# design.net
KiCad netlist of a schematic drawn in Altium Designer
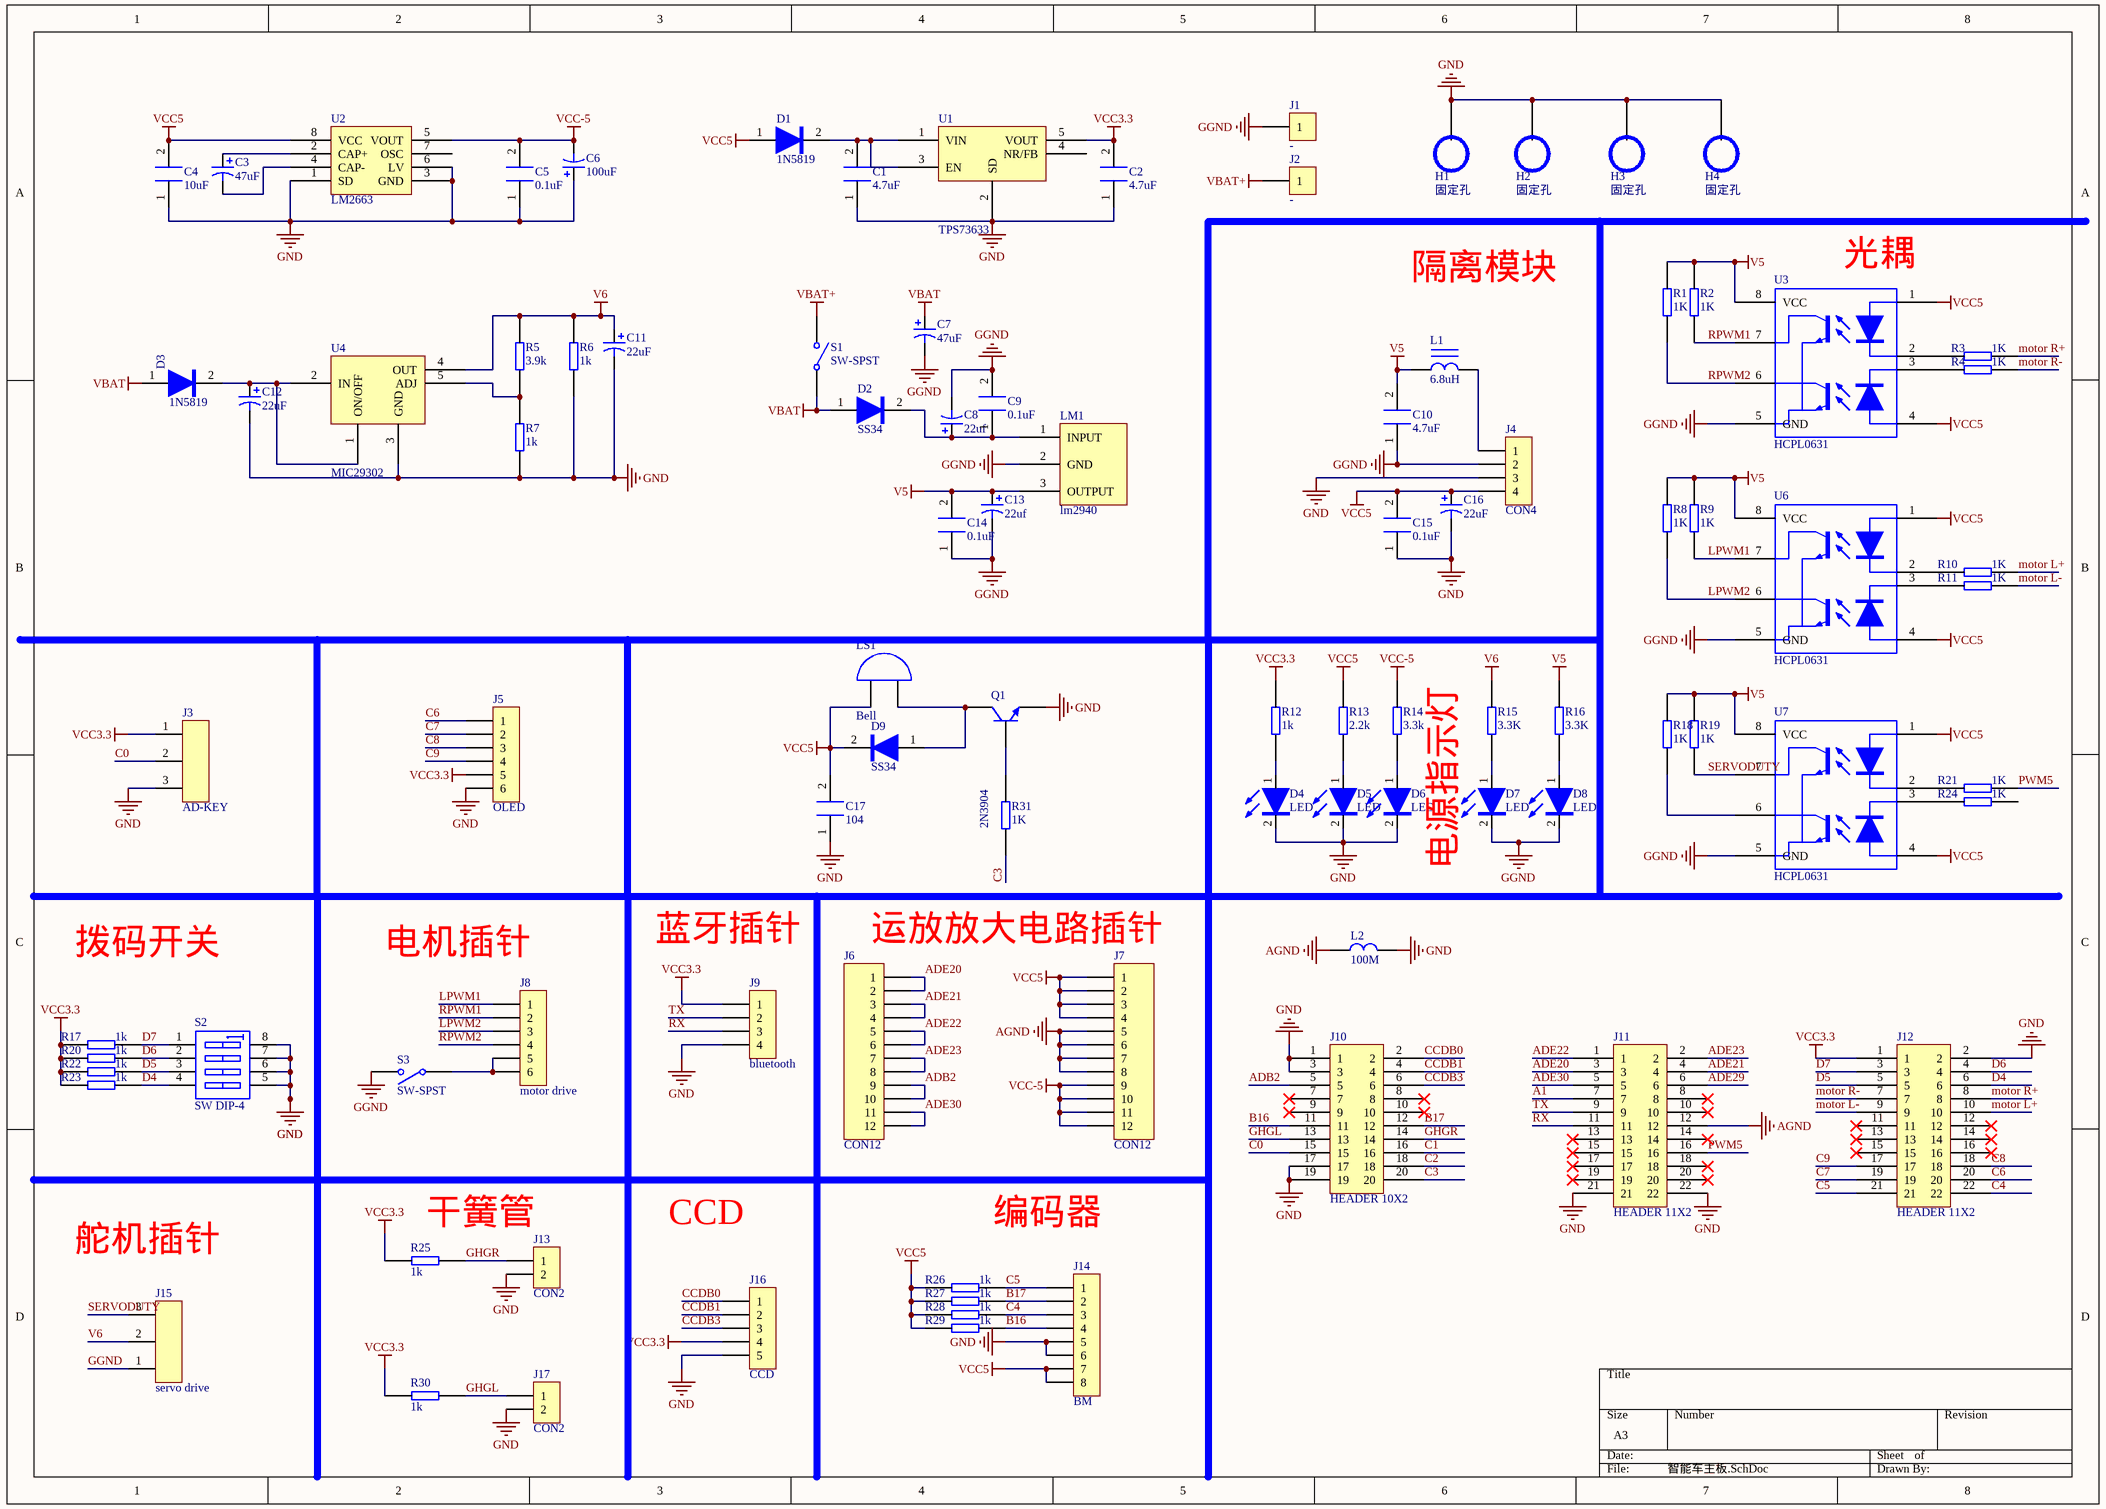
[diagram p0: 智能车主板.SchDoc]

(export (version "E")
  (design (tool "Eeschema 10.0.6"))
  (components
    (comp (ref "C1")
      (value "4.7uF")
      (footprint "0805C")
      (description "电容")
      (libsource (lib "智能车主板") (part "CAP"))
    )
    (comp (ref "C2")
      (value "4.7uF")
      (footprint "0805C")
      (description "电容")
      (libsource (lib "智能车主板") (part "CAP"))
    )
    (comp (ref "C3")
      (value "47uF")
      (footprint "C型钽电容_6032_28")
      (description "极性电容")
      (libsource (lib "智能车主板") (part "极性电容"))
    )
    (comp (ref "C4")
      (value "10uF")
      (footprint "0805C")
      (description "电容")
      (libsource (lib "智能车主板") (part "CAP"))
    )
    (comp (ref "C5")
      (value "0.1uF")
      (footprint "0805C")
      (description "电容")
      (libsource (lib "智能车主板") (part "CAP"))
    )
    (comp (ref "C6")
      (value "100uF")
      (footprint "D型钽电容_7343_31")
      (description "极性电容")
      (libsource (lib "智能车主板") (part "极性电容"))
    )
    (comp (ref "C7")
      (value "47uF")
      (footprint "D型钽电容_7343_31")
      (description "极性电容")
      (libsource (lib "") (part "极性电容_1"))
    )
    (comp (ref "C8")
      (value "22uf")
      (footprint "C型钽电容_6032_28")
      (description "极性电容")
      (libsource (lib "智能车主板") (part "极性电容"))
    )
    (comp (ref "C9")
      (value "0.1uF")
      (footprint "0805C")
      (description "电容")
      (libsource (lib "智能车主板") (part "CAP"))
    )
    (comp (ref "C10")
      (value "4.7uF")
      (footprint "0805C")
      (description "电容")
      (libsource (lib "智能车主板") (part "CAP"))
    )
    (comp (ref "C11")
      (value "22uF")
      (footprint "B型钽电容_3528_21")
      (description "极性电容")
      (libsource (lib "智能车主板") (part "极性电容"))
    )
    (comp (ref "C12")
      (value "22uF")
      (footprint "B型钽电容_3528_21")
      (description "极性电容")
      (libsource (lib "智能车主板") (part "极性电容"))
    )
    (comp (ref "C13")
      (value "22uf")
      (footprint "B型钽电容_3528_21")
      (description "极性电容")
      (libsource (lib "智能车主板") (part "极性电容"))
    )
    (comp (ref "C14")
      (value "0.1uF")
      (footprint "0805C")
      (description "电容")
      (libsource (lib "智能车主板") (part "CAP"))
    )
    (comp (ref "C15")
      (value "0.1uF")
      (footprint "0805C")
      (description "电容")
      (libsource (lib "智能车主板") (part "CAP"))
    )
    (comp (ref "C16")
      (value "22uF")
      (footprint "B型钽电容_3528_21")
      (description "极性电容")
      (libsource (lib "") (part "极性电容_1"))
    )
    (comp (ref "C17")
      (value "104")
      (footprint "0805C")
      (description "电容")
      (libsource (lib "智能车主板") (part "CAP"))
    )
    (comp (ref "D1")
      (value "1N5819")
      (footprint "0805D")
      (description "二极管")
      (libsource (lib "智能车主板") (part "SS34"))
    )
    (comp (ref "D2")
      (value "SS34")
      (footprint "0805D")
      (description "二极管")
      (libsource (lib "智能车主板") (part "SS34"))
    )
    (comp (ref "D3")
      (value "1N5819")
      (footprint "0805D")
      (description "二极管")
      (libsource (lib "智能车主板") (part "SS34"))
    )
    (comp (ref "D4") (value "LED") (footprint "0805D") (libsource (lib "智能车主板") (part "LED")))
    (comp (ref "D5") (value "LED") (footprint "0805D") (libsource (lib "智能车主板") (part "LED")))
    (comp (ref "D6") (value "LED") (footprint "0805D") (libsource (lib "智能车主板") (part "LED")))
    (comp (ref "D7") (value "LED") (footprint "0805D") (libsource (lib "智能车主板") (part "LED")))
    (comp (ref "D8") (value "LED") (footprint "0805D") (libsource (lib "智能车主板") (part "LED")))
    (comp (ref "D9")
      (value "SS34")
      (footprint "SS34_3D")
      (description "二极管")
      (libsource (lib "智能车主板") (part "SS34"))
    )
    (comp (ref "H1") (value "固定孔") (footprint "铜柱孔3") (libsource (lib "智能车主板") (part "固定孔")))
    (comp (ref "H2") (value "固定孔") (footprint "铜柱孔3") (libsource (lib "智能车主板") (part "固定孔")))
    (comp (ref "H3") (value "固定孔") (footprint "铜柱孔3") (libsource (lib "智能车主板") (part "固定孔")))
    (comp (ref "H4") (value "固定孔") (footprint "铜柱孔3") (libsource (lib "智能车主板") (part "固定孔")))
    (comp (ref "J1")
      (value "-")
      (footprint "单面焊盘2*3MM_1PIN")
      (description "Connector")
      (libsource (lib "智能车主板") (part "CON1"))
    )
    (comp (ref "J2")
      (value "-")
      (footprint "单面焊盘2*3MM_1PIN")
      (description "Connector")
      (libsource (lib "智能车主板") (part "CON1"))
    )
    (comp (ref "J3")
      (value "AD-KEY")
      (footprint "HDR1X3")
      (description "SOCKET")
      (libsource (lib "") (part "CON3_1"))
    )
    (comp (ref "J4")
      (value "CON4")
      (footprint "B0505S-2W")
      (description "Connector")
      (libsource (lib "智能车主板") (part "CON4"))
    )
    (comp (ref "J5")
      (value "OLED")
      (footprint "HDR1X6")
      (description "Connector")
      (libsource (lib "智能车主板") (part "CON6"))
    )
    (comp (ref "J6")
      (value "CON12")
      (footprint "HDR2X6")
      (description "Connector")
      (libsource (lib "智能车主板") (part "CON12"))
    )
    (comp (ref "J7")
      (value "CON12")
      (footprint "HDR2X6")
      (description "Connector")
      (libsource (lib "") (part "CON12_1"))
    )
    (comp (ref "J8")
      (value "motor drive")
      (footprint "HDR2X3")
      (description "Connector")
      (libsource (lib "智能车主板") (part "CON6"))
    )
    (comp (ref "J9")
      (value "bluetooth")
      (footprint "HDR1X4")
      (description "Connector")
      (libsource (lib "智能车主板") (part "CON4"))
    )
    (comp (ref "J10")
      (value "HEADER 10X2")
      (footprint "HDR2X10")
      (description "排针")
      (libsource (lib "智能车主板") (part "HEADER 10X2"))
    )
    (comp (ref "J11")
      (value "HEADER 11X2")
      (footprint "HDR2X11")
      (description "排针")
      (libsource (lib "智能车主板") (part "HEADER 11X2"))
    )
    (comp (ref "J12")
      (value "HEADER 11X2")
      (footprint "HDR2X11")
      (description "排针")
      (libsource (lib "智能车主板") (part "HEADER 11X2"))
    )
    (comp (ref "J13")
      (value "CON2")
      (footprint "2PIN杜邦插座_1.27mm")
      (description "Connector")
      (libsource (lib "智能车主板") (part "CON2"))
    )
    (comp (ref "J14")
      (value "BM")
      (footprint "HDR2X4")
      (description "Connector")
      (libsource (lib "智能车主板") (part "CON8"))
    )
    (comp (ref "J15")
      (value "servo drive")
      (footprint "HDR1X3")
      (description "SOCKET")
      (libsource (lib "智能车主板") (part "CON3"))
    )
    (comp (ref "J16")
      (value "CCD")
      (footprint "HDR1X5")
      (description "Connector")
      (libsource (lib "智能车主板") (part "CON5"))
    )
    (comp (ref "J17")
      (value "CON2")
      (footprint "2PIN杜邦插座_1.27mm")
      (description "Connector")
      (libsource (lib "智能车主板") (part "CON2"))
    )
    (comp (ref "L1")
      (value "6.8uH")
      (footprint "CDRH3D16_4.2*1.8")
      (description "电感")
      (libsource (lib "智能车主板") (part "INDUCTOR"))
    )
    (comp (ref "L2") (value "100M") (footprint "0603L") (libsource (lib "智能车主板") (part "INDUCTOR_2")))
    (comp (ref "LM1")
      (value "lm2940")
      (footprint "SOT-223")
      (description "IC")
      (libsource (lib "智能车主板") (part "lm2940"))
    )
    (comp (ref "LS1")
      (value "Bell")
      (footprint "蜂鸣器侧装")
      (description "Electrical Bell")
      (fields (field (name "PUBLISHER") "Altium Limited"))
      (libsource (lib "智能车主板") (part "Bell"))
    )
    (comp (ref "Q1")
      (value "2N3904")
      (footprint "TO-92A")
      (description "NPN General Purpose Amplifier")
      (fields (field (name "PUBLISHER") "Altium Limited"))
      (libsource (lib "智能车主板") (part "2N3904"))
    )
    (comp (ref "R1")
      (value "1K")
      (footprint "0805R")
      (description "电阻")
      (libsource (lib "智能车主板") (part "RES"))
    )
    (comp (ref "R2")
      (value "1K")
      (footprint "0805R")
      (description "电阻")
      (libsource (lib "智能车主板") (part "RES"))
    )
    (comp (ref "R3")
      (value "1K")
      (footprint "0805R")
      (description "电阻")
      (libsource (lib "智能车主板") (part "RES"))
    )
    (comp (ref "R4")
      (value "1K")
      (footprint "0805R")
      (description "电阻")
      (libsource (lib "智能车主板") (part "RES"))
    )
    (comp (ref "R5")
      (value "3.9k")
      (footprint "0805R")
      (description "电阻")
      (libsource (lib "智能车主板") (part "RES"))
    )
    (comp (ref "R6")
      (value "1k")
      (footprint "0805R")
      (description "电阻")
      (libsource (lib "智能车主板") (part "RES"))
    )
    (comp (ref "R7")
      (value "1k")
      (footprint "0805R")
      (description "电阻")
      (libsource (lib "智能车主板") (part "RES"))
    )
    (comp (ref "R8")
      (value "1K")
      (footprint "0805R")
      (description "电阻")
      (libsource (lib "智能车主板") (part "RES"))
    )
    (comp (ref "R9")
      (value "1K")
      (footprint "0805R")
      (description "电阻")
      (libsource (lib "智能车主板") (part "RES"))
    )
    (comp (ref "R10")
      (value "1K")
      (footprint "0805R")
      (description "电阻")
      (libsource (lib "智能车主板") (part "RES"))
    )
    (comp (ref "R11")
      (value "1K")
      (footprint "0805R")
      (description "电阻")
      (libsource (lib "智能车主板") (part "RES"))
    )
    (comp (ref "R12")
      (value "1k")
      (footprint "0603R")
      (description "电阻")
      (libsource (lib "智能车主板") (part "RES"))
    )
    (comp (ref "R13")
      (value "2.2k")
      (footprint "0603R")
      (description "电阻")
      (libsource (lib "智能车主板") (part "RES"))
    )
    (comp (ref "R14")
      (value "3.3k")
      (footprint "0603R")
      (description "电阻")
      (libsource (lib "智能车主板") (part "RES"))
    )
    (comp (ref "R15")
      (value "3.3K")
      (footprint "0603R")
      (description "电阻")
      (libsource (lib "智能车主板") (part "RES"))
    )
    (comp (ref "R16")
      (value "3.3K")
      (footprint "0603R")
      (description "电阻")
      (libsource (lib "智能车主板") (part "RES"))
    )
    (comp (ref "R17")
      (value "1k")
      (footprint "0603R")
      (description "电阻")
      (libsource (lib "智能车主板") (part "RES"))
    )
    (comp (ref "R18")
      (value "1K")
      (footprint "0805R")
      (description "电阻")
      (libsource (lib "智能车主板") (part "RES"))
    )
    (comp (ref "R19")
      (value "1K")
      (footprint "0805R")
      (description "电阻")
      (libsource (lib "智能车主板") (part "RES"))
    )
    (comp (ref "R20")
      (value "1k")
      (footprint "0603R")
      (description "电阻")
      (libsource (lib "智能车主板") (part "RES"))
    )
    (comp (ref "R21")
      (value "1K")
      (footprint "0805R")
      (description "电阻")
      (libsource (lib "智能车主板") (part "RES"))
    )
    (comp (ref "R22")
      (value "1k")
      (footprint "0603R")
      (description "电阻")
      (libsource (lib "智能车主板") (part "RES"))
    )
    (comp (ref "R23")
      (value "1k")
      (footprint "0603R")
      (description "电阻")
      (libsource (lib "智能车主板") (part "RES"))
    )
    (comp (ref "R24")
      (value "1K")
      (footprint "0805R")
      (description "电阻")
      (libsource (lib "智能车主板") (part "RES"))
    )
    (comp (ref "R25")
      (value "1k")
      (footprint "0603R")
      (description "电阻")
      (libsource (lib "智能车主板") (part "RES"))
    )
    (comp (ref "R26")
      (value "1k")
      (footprint "0805R")
      (description "电阻")
      (libsource (lib "智能车主板") (part "RES"))
    )
    (comp (ref "R27")
      (value "1k")
      (footprint "0805R")
      (description "电阻")
      (libsource (lib "智能车主板") (part "RES"))
    )
    (comp (ref "R28")
      (value "1k")
      (footprint "0805R")
      (description "电阻")
      (libsource (lib "智能车主板") (part "RES"))
    )
    (comp (ref "R29")
      (value "1k")
      (footprint "0805R")
      (description "电阻")
      (libsource (lib "智能车主板") (part "RES"))
    )
    (comp (ref "R30")
      (value "1k")
      (footprint "0603R")
      (description "电阻")
      (libsource (lib "智能车主板") (part "RES"))
    )
    (comp (ref "R31")
      (value "1K")
      (footprint "0805R")
      (description "电阻")
      (libsource (lib "智能车主板") (part "RES"))
    )
    (comp (ref "S1")
      (value "SW-SPST")
      (footprint "开关")
      (description "Single-Pole, Single-Throw Switch")
      (fields (field (name "PUBLISHER") "Altium Limited"))
      (libsource (lib "智能车主板") (part "SW-SPST"))
    )
    (comp (ref "S2")
      (value "SW DIP-4")
      (footprint "4路拨码开关")
      (description "DIP Switch")
      (libsource (lib "智能车主板") (part "SW DIP-4"))
    )
    (comp (ref "S3")
      (value "SW-SPST")
      (footprint "开关")
      (description "Single-Pole, Single-Throw Switch")
      (fields (field (name "PUBLISHER") "Altium Limited"))
      (libsource (lib "智能车主板") (part "SW-SPST"))
    )
    (comp (ref "U1")
      (value "TPS73633")
      (footprint "SOT23_5-LEADS")
      (description "IC")
      (libsource (lib "智能车主板") (part "TPS73633"))
    )
    (comp (ref "U2")
      (value "LM2663")
      (footprint "SOP_8(OPA)")
      (description "IC")
      (libsource (lib "智能车主板") (part "LM2663"))
    )
    (comp (ref "U3")
      (value "HCPL0631")
      (footprint "SOP_8(OPA)")
      (description "光耦")
      (libsource (lib "智能车主板") (part "HCPL0631"))
    )
    (comp (ref "U4")
      (value "MIC29302")
      (footprint "TO_263_5(10.5*8.4mm)")
      (description "IC")
      (libsource (lib "智能车主板") (part "MIC29302"))
    )
    (comp (ref "U6")
      (value "HCPL0631")
      (footprint "SOP_8(OPA)")
      (description "光耦")
      (libsource (lib "智能车主板") (part "HCPL0631"))
    )
    (comp (ref "U7")
      (value "HCPL0631")
      (footprint "SOP_8(OPA)")
      (description "光耦")
      (libsource (lib "智能车主板") (part "HCPL0631"))
    )
  )
  (nets
    (net (code "1") (name "/A1") (class "Default")
      (node (ref "J11") (pin "7") (pinfunction "7_7") (pintype "passive"))
    )
    (net (code "2") (name "/ADB2") (class "Default")
      (node (ref "J10") (pin "5") (pinfunction "5_5") (pintype "passive"))
      (node (ref "J6") (pin "10") (pinfunction "10_10") (pintype "passive"))
      (node (ref "J6") (pin "9") (pinfunction "9_9") (pintype "passive"))
    )
    (net (code "3") (name "/ADE20") (class "Default")
      (node (ref "J11") (pin "3") (pinfunction "3_3") (pintype "passive"))
      (node (ref "J6") (pin "1") (pinfunction "1_1") (pintype "passive"))
      (node (ref "J6") (pin "2") (pinfunction "2_2") (pintype "passive"))
    )
    (net (code "4") (name "/ADE21") (class "Default")
      (node (ref "J11") (pin "4") (pinfunction "4_4") (pintype "passive"))
      (node (ref "J6") (pin "3") (pinfunction "3_3") (pintype "passive"))
      (node (ref "J6") (pin "4") (pinfunction "4_4") (pintype "passive"))
    )
    (net (code "5") (name "/ADE22") (class "Default")
      (node (ref "J11") (pin "1") (pinfunction "1_1") (pintype "passive"))
      (node (ref "J6") (pin "5") (pinfunction "5_5") (pintype "passive"))
      (node (ref "J6") (pin "6") (pinfunction "6_6") (pintype "passive"))
    )
    (net (code "6") (name "/ADE23") (class "Default")
      (node (ref "J11") (pin "2") (pinfunction "2_2") (pintype "passive"))
      (node (ref "J6") (pin "7") (pinfunction "7_7") (pintype "passive"))
      (node (ref "J6") (pin "8") (pinfunction "8_8") (pintype "passive"))
    )
    (net (code "7") (name "/ADE29") (class "Default")
      (node (ref "J11") (pin "6") (pinfunction "6_6") (pintype "passive"))
    )
    (net (code "8") (name "/ADE30") (class "Default")
      (node (ref "J11") (pin "5") (pinfunction "5_5") (pintype "passive"))
      (node (ref "J6") (pin "11") (pinfunction "11_11") (pintype "passive"))
      (node (ref "J6") (pin "12") (pinfunction "12_12") (pintype "passive"))
    )
    (net (code "9") (name "/B16") (class "Default")
      (node (ref "J10") (pin "11") (pinfunction "11_11") (pintype "passive"))
      (node (ref "J14") (pin "4") (pinfunction "4_4") (pintype "passive"))
      (node (ref "R29") (pin "1") (pinfunction "1_1") (pintype "passive"))
    )
    (net (code "10") (name "/B17") (class "Default")
      (node (ref "J10") (pin "12") (pinfunction "12_12") (pintype "passive"))
      (node (ref "J14") (pin "2") (pinfunction "2_2") (pintype "passive"))
      (node (ref "R27") (pin "1") (pinfunction "1_1") (pintype "passive"))
    )
    (net (code "11") (name "/C0") (class "Default")
      (node (ref "J10") (pin "15") (pinfunction "15_15") (pintype "passive"))
      (node (ref "J3") (pin "2") (pinfunction "2_2") (pintype "passive"))
    )
    (net (code "12") (name "/C1") (class "Default")
      (node (ref "J10") (pin "16") (pinfunction "16_16") (pintype "passive"))
    )
    (net (code "13") (name "/C2") (class "Default")
      (node (ref "J10") (pin "18") (pinfunction "18_18") (pintype "passive"))
    )
    (net (code "14") (name "/C3") (class "Default")
      (node (ref "J10") (pin "20") (pinfunction "20_20") (pintype "passive"))
      (node (ref "R31") (pin "1") (pinfunction "1_1") (pintype "passive"))
    )
    (net (code "15") (name "/C4") (class "Default")
      (node (ref "J12") (pin "22") (pinfunction "22_22") (pintype "passive"))
      (node (ref "J14") (pin "3") (pinfunction "3_3") (pintype "passive"))
      (node (ref "R28") (pin "1") (pinfunction "1_1") (pintype "passive"))
    )
    (net (code "16") (name "/C5") (class "Default")
      (node (ref "J12") (pin "21") (pinfunction "21_21") (pintype "passive"))
      (node (ref "J14") (pin "1") (pinfunction "1_1") (pintype "passive"))
      (node (ref "R26") (pin "1") (pinfunction "1_1") (pintype "passive"))
    )
    (net (code "17") (name "/C6") (class "Default")
      (node (ref "J12") (pin "20") (pinfunction "20_20") (pintype "passive"))
      (node (ref "J5") (pin "1") (pinfunction "1_1") (pintype "passive"))
    )
    (net (code "18") (name "/C7") (class "Default")
      (node (ref "J12") (pin "19") (pinfunction "19_19") (pintype "passive"))
      (node (ref "J5") (pin "2") (pinfunction "2_2") (pintype "passive"))
    )
    (net (code "19") (name "/C8") (class "Default")
      (node (ref "J12") (pin "18") (pinfunction "18_18") (pintype "passive"))
      (node (ref "J5") (pin "3") (pinfunction "3_3") (pintype "passive"))
    )
    (net (code "20") (name "/C9") (class "Default")
      (node (ref "J12") (pin "17") (pinfunction "17_17") (pintype "passive"))
      (node (ref "J5") (pin "4") (pinfunction "4_4") (pintype "passive"))
    )
    (net (code "21") (name "/CCDB0") (class "Default")
      (node (ref "J10") (pin "2") (pinfunction "2_2") (pintype "passive"))
      (node (ref "J16") (pin "1") (pinfunction "1_1") (pintype "passive"))
    )
    (net (code "22") (name "/CCDB1") (class "Default")
      (node (ref "J10") (pin "4") (pinfunction "4_4") (pintype "passive"))
      (node (ref "J16") (pin "2") (pinfunction "2_2") (pintype "passive"))
    )
    (net (code "23") (name "/CCDB3") (class "Default")
      (node (ref "J10") (pin "6") (pinfunction "6_6") (pintype "passive"))
      (node (ref "J16") (pin "3") (pinfunction "3_3") (pintype "passive"))
    )
    (net (code "24") (name "/D4") (class "Default")
      (node (ref "J12") (pin "6") (pinfunction "6_6") (pintype "passive"))
      (node (ref "R23") (pin "1") (pinfunction "1_1") (pintype "passive"))
      (node (ref "S2") (pin "4") (pinfunction "A4_4") (pintype "passive"))
    )
    (net (code "25") (name "/D5") (class "Default")
      (node (ref "J12") (pin "5") (pinfunction "5_5") (pintype "passive"))
      (node (ref "R22") (pin "1") (pinfunction "1_1") (pintype "passive"))
      (node (ref "S2") (pin "3") (pinfunction "A3_3") (pintype "passive"))
    )
    (net (code "26") (name "/D6") (class "Default")
      (node (ref "J12") (pin "4") (pinfunction "4_4") (pintype "passive"))
      (node (ref "R20") (pin "1") (pinfunction "1_1") (pintype "passive"))
      (node (ref "S2") (pin "2") (pinfunction "A2_2") (pintype "passive"))
    )
    (net (code "27") (name "/D7") (class "Default")
      (node (ref "J12") (pin "3") (pinfunction "3_3") (pintype "passive"))
      (node (ref "R17") (pin "1") (pinfunction "1_1") (pintype "passive"))
      (node (ref "S2") (pin "1") (pinfunction "A1_1") (pintype "passive"))
    )
    (net (code "28") (name "/GHGL") (class "Default")
      (node (ref "J10") (pin "13") (pinfunction "13_13") (pintype "passive"))
      (node (ref "J17") (pin "1") (pinfunction "1_1") (pintype "passive"))
      (node (ref "R30") (pin "1") (pinfunction "1_1") (pintype "passive"))
    )
    (net (code "29") (name "/GHGR") (class "Default")
      (node (ref "J10") (pin "14") (pinfunction "14_14") (pintype "passive"))
      (node (ref "J13") (pin "1") (pinfunction "1_1") (pintype "passive"))
      (node (ref "R25") (pin "1") (pinfunction "1_1") (pintype "passive"))
    )
    (net (code "30") (name "/LPWM1") (class "Default")
      (node (ref "J8") (pin "1") (pinfunction "1_1") (pintype "passive"))
      (node (ref "R9") (pin "1") (pinfunction "1_1") (pintype "passive"))
      (node (ref "U6") (pin "7") (pinfunction "7_7") (pintype "passive"))
    )
    (net (code "31") (name "/LPWM2") (class "Default")
      (node (ref "J8") (pin "3") (pinfunction "3_3") (pintype "passive"))
      (node (ref "R8") (pin "1") (pinfunction "1_1") (pintype "passive"))
      (node (ref "U6") (pin "6") (pinfunction "6_6") (pintype "passive"))
    )
    (net (code "32") (name "/PWM5") (class "Default")
      (node (ref "J11") (pin "16") (pinfunction "16_16") (pintype "passive"))
      (node (ref "R21") (pin "1") (pinfunction "1_1") (pintype "passive"))
    )
    (net (code "33") (name "/RPWM1") (class "Default")
      (node (ref "J8") (pin "2") (pinfunction "2_2") (pintype "passive"))
      (node (ref "R2") (pin "1") (pinfunction "1_1") (pintype "passive"))
      (node (ref "U3") (pin "7") (pinfunction "7_7") (pintype "passive"))
    )
    (net (code "34") (name "/RPWM2") (class "Default")
      (node (ref "J8") (pin "4") (pinfunction "4_4") (pintype "passive"))
      (node (ref "R1") (pin "1") (pinfunction "1_1") (pintype "passive"))
      (node (ref "U3") (pin "6") (pinfunction "6_6") (pintype "passive"))
    )
    (net (code "35") (name "/RX") (class "Default")
      (node (ref "J11") (pin "11") (pinfunction "11_11") (pintype "passive"))
      (node (ref "J9") (pin "3") (pinfunction "3_3") (pintype "passive"))
    )
    (net (code "36") (name "/SERVODUTY") (class "Default")
      (node (ref "J15") (pin "3") (pinfunction "3_3") (pintype "passive"))
      (node (ref "R19") (pin "1") (pinfunction "1_1") (pintype "passive"))
      (node (ref "U7") (pin "7") (pinfunction "7_7") (pintype "passive"))
    )
    (net (code "37") (name "/TX") (class "Default")
      (node (ref "J11") (pin "9") (pinfunction "9_9") (pintype "passive"))
      (node (ref "J9") (pin "2") (pinfunction "2_2") (pintype "passive"))
    )
    (net (code "38") (name "/motor L+") (class "Default")
      (node (ref "J12") (pin "10") (pinfunction "10_10") (pintype "passive"))
      (node (ref "R10") (pin "1") (pinfunction "1_1") (pintype "passive"))
    )
    (net (code "39") (name "/motor L-") (class "Default")
      (node (ref "J12") (pin "9") (pinfunction "9_9") (pintype "passive"))
      (node (ref "R11") (pin "1") (pinfunction "1_1") (pintype "passive"))
    )
    (net (code "40") (name "/motor R+") (class "Default")
      (node (ref "J12") (pin "8") (pinfunction "8_8") (pintype "passive"))
      (node (ref "R3") (pin "1") (pinfunction "1_1") (pintype "passive"))
    )
    (net (code "41") (name "/motor R-") (class "Default")
      (node (ref "J12") (pin "7") (pinfunction "7_7") (pintype "passive"))
      (node (ref "R4") (pin "1") (pinfunction "1_1") (pintype "passive"))
    )
    (net (code "42") (name "AGND") (class "Default")
      (node (ref "J11") (pin "12") (pinfunction "12_12") (pintype "passive"))
      (node (ref "J7") (pin "5") (pinfunction "5_5") (pintype "passive"))
      (node (ref "J7") (pin "6") (pinfunction "6_6") (pintype "passive"))
      (node (ref "J7") (pin "7") (pinfunction "7_7") (pintype "passive"))
      (node (ref "J7") (pin "8") (pinfunction "8_8") (pintype "passive"))
      (node (ref "L2") (pin "1") (pinfunction "1_1") (pintype "passive"))
    )
    (net (code "43") (name "GGND") (class "Default")
      (node (ref "C10") (pin "1") (pinfunction "1_1") (pintype "passive"))
      (node (ref "C13") (pin "2") (pinfunction "2_2") (pintype "passive"))
      (node (ref "C14") (pin "1") (pinfunction "1_1") (pintype "passive"))
      (node (ref "C7") (pin "2") (pinfunction "2_2") (pintype "passive"))
      (node (ref "C8") (pin "2") (pinfunction "2_2") (pintype "passive"))
      (node (ref "C9") (pin "2") (pinfunction "2_2") (pintype "passive"))
      (node (ref "D7") (pin "2") (pinfunction "2_2") (pintype "passive"))
      (node (ref "D8") (pin "2") (pinfunction "2_2") (pintype "passive"))
      (node (ref "J1") (pin "1") (pinfunction "1_1") (pintype "passive"))
      (node (ref "J15") (pin "1") (pinfunction "1_1") (pintype "passive"))
      (node (ref "J4") (pin "2") (pinfunction "2_2") (pintype "passive"))
      (node (ref "LM1") (pin "2") (pinfunction "GND_2") (pintype "passive"))
      (node (ref "S3") (pin "2") (pinfunction "NO_2") (pintype "passive"))
      (node (ref "U3") (pin "5") (pinfunction "GND_5") (pintype "passive"))
      (node (ref "U6") (pin "5") (pinfunction "GND_5") (pintype "passive"))
      (node (ref "U7") (pin "5") (pinfunction "GND_5") (pintype "passive"))
    )
    (net (code "44") (name "GND") (class "Default")
      (node (ref "C1") (pin "1") (pinfunction "1_1") (pintype "passive"))
      (node (ref "C11") (pin "2") (pinfunction "2_2") (pintype "passive"))
      (node (ref "C12") (pin "2") (pinfunction "2_2") (pintype "passive"))
      (node (ref "C15") (pin "1") (pinfunction "1_1") (pintype "passive"))
      (node (ref "C16") (pin "2") (pinfunction "2_2") (pintype "passive"))
      (node (ref "C17") (pin "1") (pinfunction "1_1") (pintype "passive"))
      (node (ref "C2") (pin "1") (pinfunction "1_1") (pintype "passive"))
      (node (ref "C4") (pin "1") (pinfunction "1_1") (pintype "passive"))
      (node (ref "C5") (pin "1") (pinfunction "1_1") (pintype "passive"))
      (node (ref "C6") (pin "1") (pinfunction "1_1") (pintype "passive"))
      (node (ref "D4") (pin "2") (pinfunction "2_2") (pintype "passive"))
      (node (ref "D5") (pin "2") (pinfunction "2_2") (pintype "passive"))
      (node (ref "D6") (pin "2") (pinfunction "2_2") (pintype "passive"))
      (node (ref "H1") (pin "11") (pinfunction "11_11") (pintype "passive"))
      (node (ref "H2") (pin "11") (pinfunction "11_11") (pintype "passive"))
      (node (ref "H3") (pin "11") (pinfunction "11_11") (pintype "passive"))
      (node (ref "H4") (pin "11") (pinfunction "11_11") (pintype "passive"))
      (node (ref "J10") (pin "1") (pinfunction "1_1") (pintype "passive"))
      (node (ref "J10") (pin "17") (pinfunction "17_17") (pintype "passive"))
      (node (ref "J10") (pin "19") (pinfunction "19_19") (pintype "passive"))
      (node (ref "J10") (pin "3") (pinfunction "3_3") (pintype "passive"))
      (node (ref "J11") (pin "21") (pinfunction "21_21") (pintype "passive"))
      (node (ref "J11") (pin "22") (pinfunction "22_22") (pintype "passive"))
      (node (ref "J12") (pin "2") (pinfunction "2_2") (pintype "passive"))
      (node (ref "J13") (pin "2") (pinfunction "2_2") (pintype "passive"))
      (node (ref "J14") (pin "5") (pinfunction "5_5") (pintype "passive"))
      (node (ref "J14") (pin "6") (pinfunction "6_6") (pintype "passive"))
      (node (ref "J16") (pin "5") (pinfunction "5_5") (pintype "passive"))
      (node (ref "J17") (pin "2") (pinfunction "2_2") (pintype "passive"))
      (node (ref "J3") (pin "3") (pinfunction "3_3") (pintype "passive"))
      (node (ref "J4") (pin "3") (pinfunction "3_3") (pintype "passive"))
      (node (ref "J5") (pin "6") (pinfunction "6_6") (pintype "passive"))
      (node (ref "J9") (pin "4") (pinfunction "4_4") (pintype "passive"))
      (node (ref "L2") (pin "2") (pinfunction "2_2") (pintype "passive"))
      (node (ref "Q1") (pin "1") (pinfunction "E_1") (pintype "passive"))
      (node (ref "R6") (pin "1") (pinfunction "1_1") (pintype "passive"))
      (node (ref "R7") (pin "1") (pinfunction "1_1") (pintype "passive"))
      (node (ref "S2") (pin "5") (pinfunction "B4_5") (pintype "passive"))
      (node (ref "S2") (pin "6") (pinfunction "B3_6") (pintype "passive"))
      (node (ref "S2") (pin "7") (pinfunction "B2_7") (pintype "passive"))
      (node (ref "S2") (pin "8") (pinfunction "B1_8") (pintype "passive"))
      (node (ref "U1") (pin "2") (pinfunction "SD_2") (pintype "passive"))
      (node (ref "U2") (pin "1") (pinfunction "SD_1") (pintype "passive"))
      (node (ref "U2") (pin "3") (pinfunction "GND_3") (pintype "passive"))
      (node (ref "U2") (pin "6") (pinfunction "LV_6") (pintype "passive"))
      (node (ref "U4") (pin "3") (pinfunction "GND_3") (pintype "passive"))
    )
    (net (code "45") (name "Net-(D4-Pad1)") (class "Default")
      (node (ref "D4") (pin "1") (pinfunction "1_1") (pintype "passive"))
      (node (ref "R12") (pin "1") (pinfunction "1_1") (pintype "passive"))
    )
    (net (code "46") (name "Net-(D5-Pad1)") (class "Default")
      (node (ref "D5") (pin "1") (pinfunction "1_1") (pintype "passive"))
      (node (ref "R13") (pin "1") (pinfunction "1_1") (pintype "passive"))
    )
    (net (code "47") (name "Net-(D6-Pad1)") (class "Default")
      (node (ref "D6") (pin "1") (pinfunction "1_1") (pintype "passive"))
      (node (ref "R14") (pin "1") (pinfunction "1_1") (pintype "passive"))
    )
    (net (code "48") (name "Net-(D7-Pad1)") (class "Default")
      (node (ref "D7") (pin "1") (pinfunction "1_1") (pintype "passive"))
      (node (ref "R15") (pin "1") (pinfunction "1_1") (pintype "passive"))
    )
    (net (code "49") (name "Net-(D8-Pad1)") (class "Default")
      (node (ref "D8") (pin "1") (pinfunction "1_1") (pintype "passive"))
      (node (ref "R16") (pin "1") (pinfunction "1_1") (pintype "passive"))
    )
    (net (code "50") (name "Net-(J4-Pad1)") (class "Default")
      (node (ref "J4") (pin "1") (pinfunction "1_1") (pintype "passive"))
      (node (ref "L1") (pin "2") (pinfunction "2_2") (pintype "passive"))
    )
    (net (code "51") (name "Net-(LM1-INPUT)") (class "Default")
      (node (ref "C8") (pin "1") (pinfunction "1_1") (pintype "passive"))
      (node (ref "C9") (pin "1") (pinfunction "1_1") (pintype "passive"))
      (node (ref "D2") (pin "2") (pinfunction "2_2") (pintype "passive"))
      (node (ref "LM1") (pin "1") (pinfunction "INPUT_1") (pintype "passive"))
    )
    (net (code "52") (name "Net-(LS1-B)") (class "Default")
      (node (ref "D9") (pin "1") (pinfunction "1_1") (pintype "passive"))
      (node (ref "LS1") (pin "2") (pinfunction "B_2") (pintype "passive"))
      (node (ref "Q1") (pin "3") (pinfunction "C_3") (pintype "passive"))
    )
    (net (code "53") (name "Net-(Q1-B)") (class "Default")
      (node (ref "Q1") (pin "2") (pinfunction "B_2") (pintype "passive"))
      (node (ref "R31") (pin "2") (pinfunction "2_2") (pintype "passive"))
    )
    (net (code "54") (name "Net-(R3-Pad2)") (class "Default")
      (node (ref "R3") (pin "2") (pinfunction "2_2") (pintype "passive"))
      (node (ref "U3") (pin "2") (pinfunction "2_2") (pintype "passive"))
    )
    (net (code "55") (name "Net-(R4-Pad2)") (class "Default")
      (node (ref "R4") (pin "2") (pinfunction "2_2") (pintype "passive"))
      (node (ref "U3") (pin "3") (pinfunction "3_3") (pintype "passive"))
    )
    (net (code "56") (name "Net-(R10-Pad2)") (class "Default")
      (node (ref "R10") (pin "2") (pinfunction "2_2") (pintype "passive"))
      (node (ref "U6") (pin "2") (pinfunction "2_2") (pintype "passive"))
    )
    (net (code "57") (name "Net-(R11-Pad2)") (class "Default")
      (node (ref "R11") (pin "2") (pinfunction "2_2") (pintype "passive"))
      (node (ref "U6") (pin "3") (pinfunction "3_3") (pintype "passive"))
    )
    (net (code "58") (name "Net-(R18-Pad1)") (class "Default")
      (node (ref "R18") (pin "1") (pinfunction "1_1") (pintype "passive"))
      (node (ref "U7") (pin "6") (pinfunction "6_6") (pintype "passive"))
    )
    (net (code "59") (name "Net-(R21-Pad2)") (class "Default")
      (node (ref "R21") (pin "2") (pinfunction "2_2") (pintype "passive"))
      (node (ref "U7") (pin "2") (pinfunction "2_2") (pintype "passive"))
    )
    (net (code "60") (name "Net-(R24-Pad2)") (class "Default")
      (node (ref "R24") (pin "2") (pinfunction "2_2") (pintype "passive"))
      (node (ref "U7") (pin "3") (pinfunction "3_3") (pintype "passive"))
    )
    (net (code "61") (name "Net-(S3-COMMON)") (class "Default")
      (node (ref "J8") (pin "5") (pinfunction "5_5") (pintype "passive"))
      (node (ref "J8") (pin "6") (pinfunction "6_6") (pintype "passive"))
      (node (ref "S3") (pin "1") (pinfunction "COMMON_1") (pintype "passive"))
    )
    (net (code "62") (name "Net-(U1-EN)") (class "Default")
      (node (ref "C1") (pin "2") (pinfunction "2_2") (pintype "passive"))
      (node (ref "D1") (pin "2") (pinfunction "2_2") (pintype "passive"))
      (node (ref "U1") (pin "1") (pinfunction "VIN_1") (pintype "passive"))
      (node (ref "U1") (pin "3") (pinfunction "EN_3") (pintype "passive"))
    )
    (net (code "63") (name "Net-(U2-CAP+)") (class "Default")
      (node (ref "C3") (pin "1") (pinfunction "1_1") (pintype "passive"))
      (node (ref "U2") (pin "2") (pinfunction "CAP+_2") (pintype "passive"))
    )
    (net (code "64") (name "Net-(U2-CAP-)") (class "Default")
      (node (ref "C3") (pin "2") (pinfunction "2_2") (pintype "passive"))
      (node (ref "U2") (pin "4") (pinfunction "CAP-_4") (pintype "passive"))
    )
    (net (code "65") (name "Net-(U4-ADJ)") (class "Default")
      (node (ref "R5") (pin "1") (pinfunction "1_1") (pintype "passive"))
      (node (ref "R7") (pin "2") (pinfunction "2_2") (pintype "passive"))
      (node (ref "U4") (pin "5") (pinfunction "ADJ_5") (pintype "passive"))
    )
    (net (code "66") (name "Net-(U4-IN)") (class "Default")
      (node (ref "C12") (pin "1") (pinfunction "1_1") (pintype "passive"))
      (node (ref "D3") (pin "2") (pinfunction "2_2") (pintype "passive"))
      (node (ref "U4") (pin "1") (pinfunction "ON/OFF_1") (pintype "passive"))
      (node (ref "U4") (pin "2") (pinfunction "IN_2") (pintype "passive"))
    )
    (net (code "67") (name "V5") (class "Default")
      (node (ref "C10") (pin "2") (pinfunction "2_2") (pintype "passive"))
      (node (ref "C13") (pin "1") (pinfunction "1_1") (pintype "passive"))
      (node (ref "C14") (pin "2") (pinfunction "2_2") (pintype "passive"))
      (node (ref "L1") (pin "1") (pinfunction "1_1") (pintype "passive"))
      (node (ref "LM1") (pin "3") (pinfunction "OUTPUT_3") (pintype "passive"))
      (node (ref "R1") (pin "2") (pinfunction "2_2") (pintype "passive"))
      (node (ref "R16") (pin "2") (pinfunction "2_2") (pintype "passive"))
      (node (ref "R18") (pin "2") (pinfunction "2_2") (pintype "passive"))
      (node (ref "R19") (pin "2") (pinfunction "2_2") (pintype "passive"))
      (node (ref "R2") (pin "2") (pinfunction "2_2") (pintype "passive"))
      (node (ref "R8") (pin "2") (pinfunction "2_2") (pintype "passive"))
      (node (ref "R9") (pin "2") (pinfunction "2_2") (pintype "passive"))
      (node (ref "U3") (pin "8") (pinfunction "VCC_8") (pintype "passive"))
      (node (ref "U6") (pin "8") (pinfunction "VCC_8") (pintype "passive"))
      (node (ref "U7") (pin "8") (pinfunction "VCC_8") (pintype "passive"))
    )
    (net (code "68") (name "V6") (class "Default")
      (node (ref "C11") (pin "1") (pinfunction "1_1") (pintype "passive"))
      (node (ref "J15") (pin "2") (pinfunction "2_2") (pintype "passive"))
      (node (ref "R15") (pin "2") (pinfunction "2_2") (pintype "passive"))
      (node (ref "R5") (pin "2") (pinfunction "2_2") (pintype "passive"))
      (node (ref "R6") (pin "2") (pinfunction "2_2") (pintype "passive"))
      (node (ref "U4") (pin "4") (pinfunction "OUT_4") (pintype "passive"))
    )
    (net (code "69") (name "VBAT") (class "Default")
      (node (ref "C7") (pin "1") (pinfunction "1_1") (pintype "passive"))
      (node (ref "D2") (pin "1") (pinfunction "1_1") (pintype "passive"))
      (node (ref "D3") (pin "1") (pinfunction "1_1") (pintype "passive"))
      (node (ref "S1") (pin "1") (pinfunction "COMMON_1") (pintype "passive"))
    )
    (net (code "70") (name "VBAT+") (class "Default")
      (node (ref "J2") (pin "1") (pinfunction "1_1") (pintype "passive"))
      (node (ref "S1") (pin "2") (pinfunction "NO_2") (pintype "passive"))
    )
    (net (code "71") (name "VCC-5") (class "Default")
      (node (ref "C5") (pin "2") (pinfunction "2_2") (pintype "passive"))
      (node (ref "C6") (pin "2") (pinfunction "2_2") (pintype "passive"))
      (node (ref "J7") (pin "10") (pinfunction "10_10") (pintype "passive"))
      (node (ref "J7") (pin "11") (pinfunction "11_11") (pintype "passive"))
      (node (ref "J7") (pin "12") (pinfunction "12_12") (pintype "passive"))
      (node (ref "J7") (pin "9") (pinfunction "9_9") (pintype "passive"))
      (node (ref "R14") (pin "2") (pinfunction "2_2") (pintype "passive"))
      (node (ref "U2") (pin "5") (pinfunction "VOUT_5") (pintype "passive"))
    )
    (net (code "72") (name "VCC3.3") (class "Default")
      (node (ref "C2") (pin "2") (pinfunction "2_2") (pintype "passive"))
      (node (ref "J12") (pin "1") (pinfunction "1_1") (pintype "passive"))
      (node (ref "J16") (pin "4") (pinfunction "4_4") (pintype "passive"))
      (node (ref "J3") (pin "1") (pinfunction "1_1") (pintype "passive"))
      (node (ref "J5") (pin "5") (pinfunction "5_5") (pintype "passive"))
      (node (ref "J9") (pin "1") (pinfunction "1_1") (pintype "passive"))
      (node (ref "R12") (pin "2") (pinfunction "2_2") (pintype "passive"))
      (node (ref "R17") (pin "2") (pinfunction "2_2") (pintype "passive"))
      (node (ref "R20") (pin "2") (pinfunction "2_2") (pintype "passive"))
      (node (ref "R22") (pin "2") (pinfunction "2_2") (pintype "passive"))
      (node (ref "R23") (pin "2") (pinfunction "2_2") (pintype "passive"))
      (node (ref "R25") (pin "2") (pinfunction "2_2") (pintype "passive"))
      (node (ref "R30") (pin "2") (pinfunction "2_2") (pintype "passive"))
      (node (ref "U1") (pin "5") (pinfunction "VOUT_5") (pintype "passive"))
    )
    (net (code "73") (name "VCC5") (class "Default")
      (node (ref "C15") (pin "2") (pinfunction "2_2") (pintype "passive"))
      (node (ref "C16") (pin "1") (pinfunction "1_1") (pintype "passive"))
      (node (ref "C17") (pin "2") (pinfunction "2_2") (pintype "passive"))
      (node (ref "C4") (pin "2") (pinfunction "2_2") (pintype "passive"))
      (node (ref "D1") (pin "1") (pinfunction "1_1") (pintype "passive"))
      (node (ref "D9") (pin "2") (pinfunction "2_2") (pintype "passive"))
      (node (ref "J14") (pin "7") (pinfunction "7_7") (pintype "passive"))
      (node (ref "J14") (pin "8") (pinfunction "8_8") (pintype "passive"))
      (node (ref "J4") (pin "4") (pinfunction "4_4") (pintype "passive"))
      (node (ref "J7") (pin "1") (pinfunction "1_1") (pintype "passive"))
      (node (ref "J7") (pin "2") (pinfunction "2_2") (pintype "passive"))
      (node (ref "J7") (pin "3") (pinfunction "3_3") (pintype "passive"))
      (node (ref "J7") (pin "4") (pinfunction "4_4") (pintype "passive"))
      (node (ref "LS1") (pin "1") (pinfunction "A_1") (pintype "passive"))
      (node (ref "R13") (pin "2") (pinfunction "2_2") (pintype "passive"))
      (node (ref "R26") (pin "2") (pinfunction "2_2") (pintype "passive"))
      (node (ref "R27") (pin "2") (pinfunction "2_2") (pintype "passive"))
      (node (ref "R28") (pin "2") (pinfunction "2_2") (pintype "passive"))
      (node (ref "R29") (pin "2") (pinfunction "2_2") (pintype "passive"))
      (node (ref "U2") (pin "8") (pinfunction "VCC_8") (pintype "passive"))
      (node (ref "U3") (pin "1") (pinfunction "1_1") (pintype "passive"))
      (node (ref "U3") (pin "4") (pinfunction "4_4") (pintype "passive"))
      (node (ref "U6") (pin "1") (pinfunction "1_1") (pintype "passive"))
      (node (ref "U6") (pin "4") (pinfunction "4_4") (pintype "passive"))
      (node (ref "U7") (pin "1") (pinfunction "1_1") (pintype "passive"))
      (node (ref "U7") (pin "4") (pinfunction "4_4") (pintype "passive"))
    )
    (net (code "74") (name "unconnected-(J10-Pad7)") (class "Default")
      (node (ref "J10") (pin "7") (pinfunction "7_7") (pintype "passive+no_connect"))
    )
    (net (code "75") (name "unconnected-(J10-Pad8)") (class "Default")
      (node (ref "J10") (pin "8") (pinfunction "8_8") (pintype "passive+no_connect"))
    )
    (net (code "76") (name "unconnected-(J10-Pad9)") (class "Default")
      (node (ref "J10") (pin "9") (pinfunction "9_9") (pintype "passive+no_connect"))
    )
    (net (code "77") (name "unconnected-(J10-Pad10)") (class "Default")
      (node (ref "J10") (pin "10") (pinfunction "10_10") (pintype "passive+no_connect"))
    )
    (net (code "78") (name "unconnected-(J11-Pad8)") (class "Default")
      (node (ref "J11") (pin "8") (pinfunction "8_8") (pintype "passive+no_connect"))
    )
    (net (code "79") (name "unconnected-(J11-Pad10)") (class "Default")
      (node (ref "J11") (pin "10") (pinfunction "10_10") (pintype "passive+no_connect"))
    )
    (net (code "80") (name "unconnected-(J11-Pad13)") (class "Default")
      (node (ref "J11") (pin "13") (pinfunction "13_13") (pintype "passive+no_connect"))
    )
    (net (code "81") (name "unconnected-(J11-Pad14)") (class "Default")
      (node (ref "J11") (pin "14") (pinfunction "14_14") (pintype "passive+no_connect"))
    )
    (net (code "82") (name "unconnected-(J11-Pad15)") (class "Default")
      (node (ref "J11") (pin "15") (pinfunction "15_15") (pintype "passive+no_connect"))
    )
    (net (code "83") (name "unconnected-(J11-Pad17)") (class "Default")
      (node (ref "J11") (pin "17") (pinfunction "17_17") (pintype "passive+no_connect"))
    )
    (net (code "84") (name "unconnected-(J11-Pad18)") (class "Default")
      (node (ref "J11") (pin "18") (pinfunction "18_18") (pintype "passive+no_connect"))
    )
    (net (code "85") (name "unconnected-(J11-Pad19)") (class "Default")
      (node (ref "J11") (pin "19") (pinfunction "19_19") (pintype "passive+no_connect"))
    )
    (net (code "86") (name "unconnected-(J11-Pad20)") (class "Default")
      (node (ref "J11") (pin "20") (pinfunction "20_20") (pintype "passive+no_connect"))
    )
    (net (code "87") (name "unconnected-(J12-Pad11)") (class "Default")
      (node (ref "J12") (pin "11") (pinfunction "11_11") (pintype "passive+no_connect"))
    )
    (net (code "88") (name "unconnected-(J12-Pad12)") (class "Default")
      (node (ref "J12") (pin "12") (pinfunction "12_12") (pintype "passive+no_connect"))
    )
    (net (code "89") (name "unconnected-(J12-Pad13)") (class "Default")
      (node (ref "J12") (pin "13") (pinfunction "13_13") (pintype "passive+no_connect"))
    )
    (net (code "90") (name "unconnected-(J12-Pad14)") (class "Default")
      (node (ref "J12") (pin "14") (pinfunction "14_14") (pintype "passive+no_connect"))
    )
    (net (code "91") (name "unconnected-(J12-Pad15)") (class "Default")
      (node (ref "J12") (pin "15") (pinfunction "15_15") (pintype "passive+no_connect"))
    )
    (net (code "92") (name "unconnected-(J12-Pad16)") (class "Default")
      (node (ref "J12") (pin "16") (pinfunction "16_16") (pintype "passive+no_connect"))
    )
    (net (code "93") (name "unconnected-(R24-Pad1)") (class "Default")
      (node (ref "R24") (pin "1") (pinfunction "1_1") (pintype "passive"))
    )
    (net (code "94") (name "unconnected-(U1-NR{slash}FB-Pad4)") (class "Default")
      (node (ref "U1") (pin "4") (pinfunction "NR/FB_4") (pintype "passive"))
    )
    (net (code "95") (name "unconnected-(U2-OSC-Pad7)") (class "Default")
      (node (ref "U2") (pin "7") (pinfunction "OSC_7") (pintype "passive"))
    )
  )
)
